# T03_Schematic.net
KiCad netlist of a schematic drawn in EAGLE
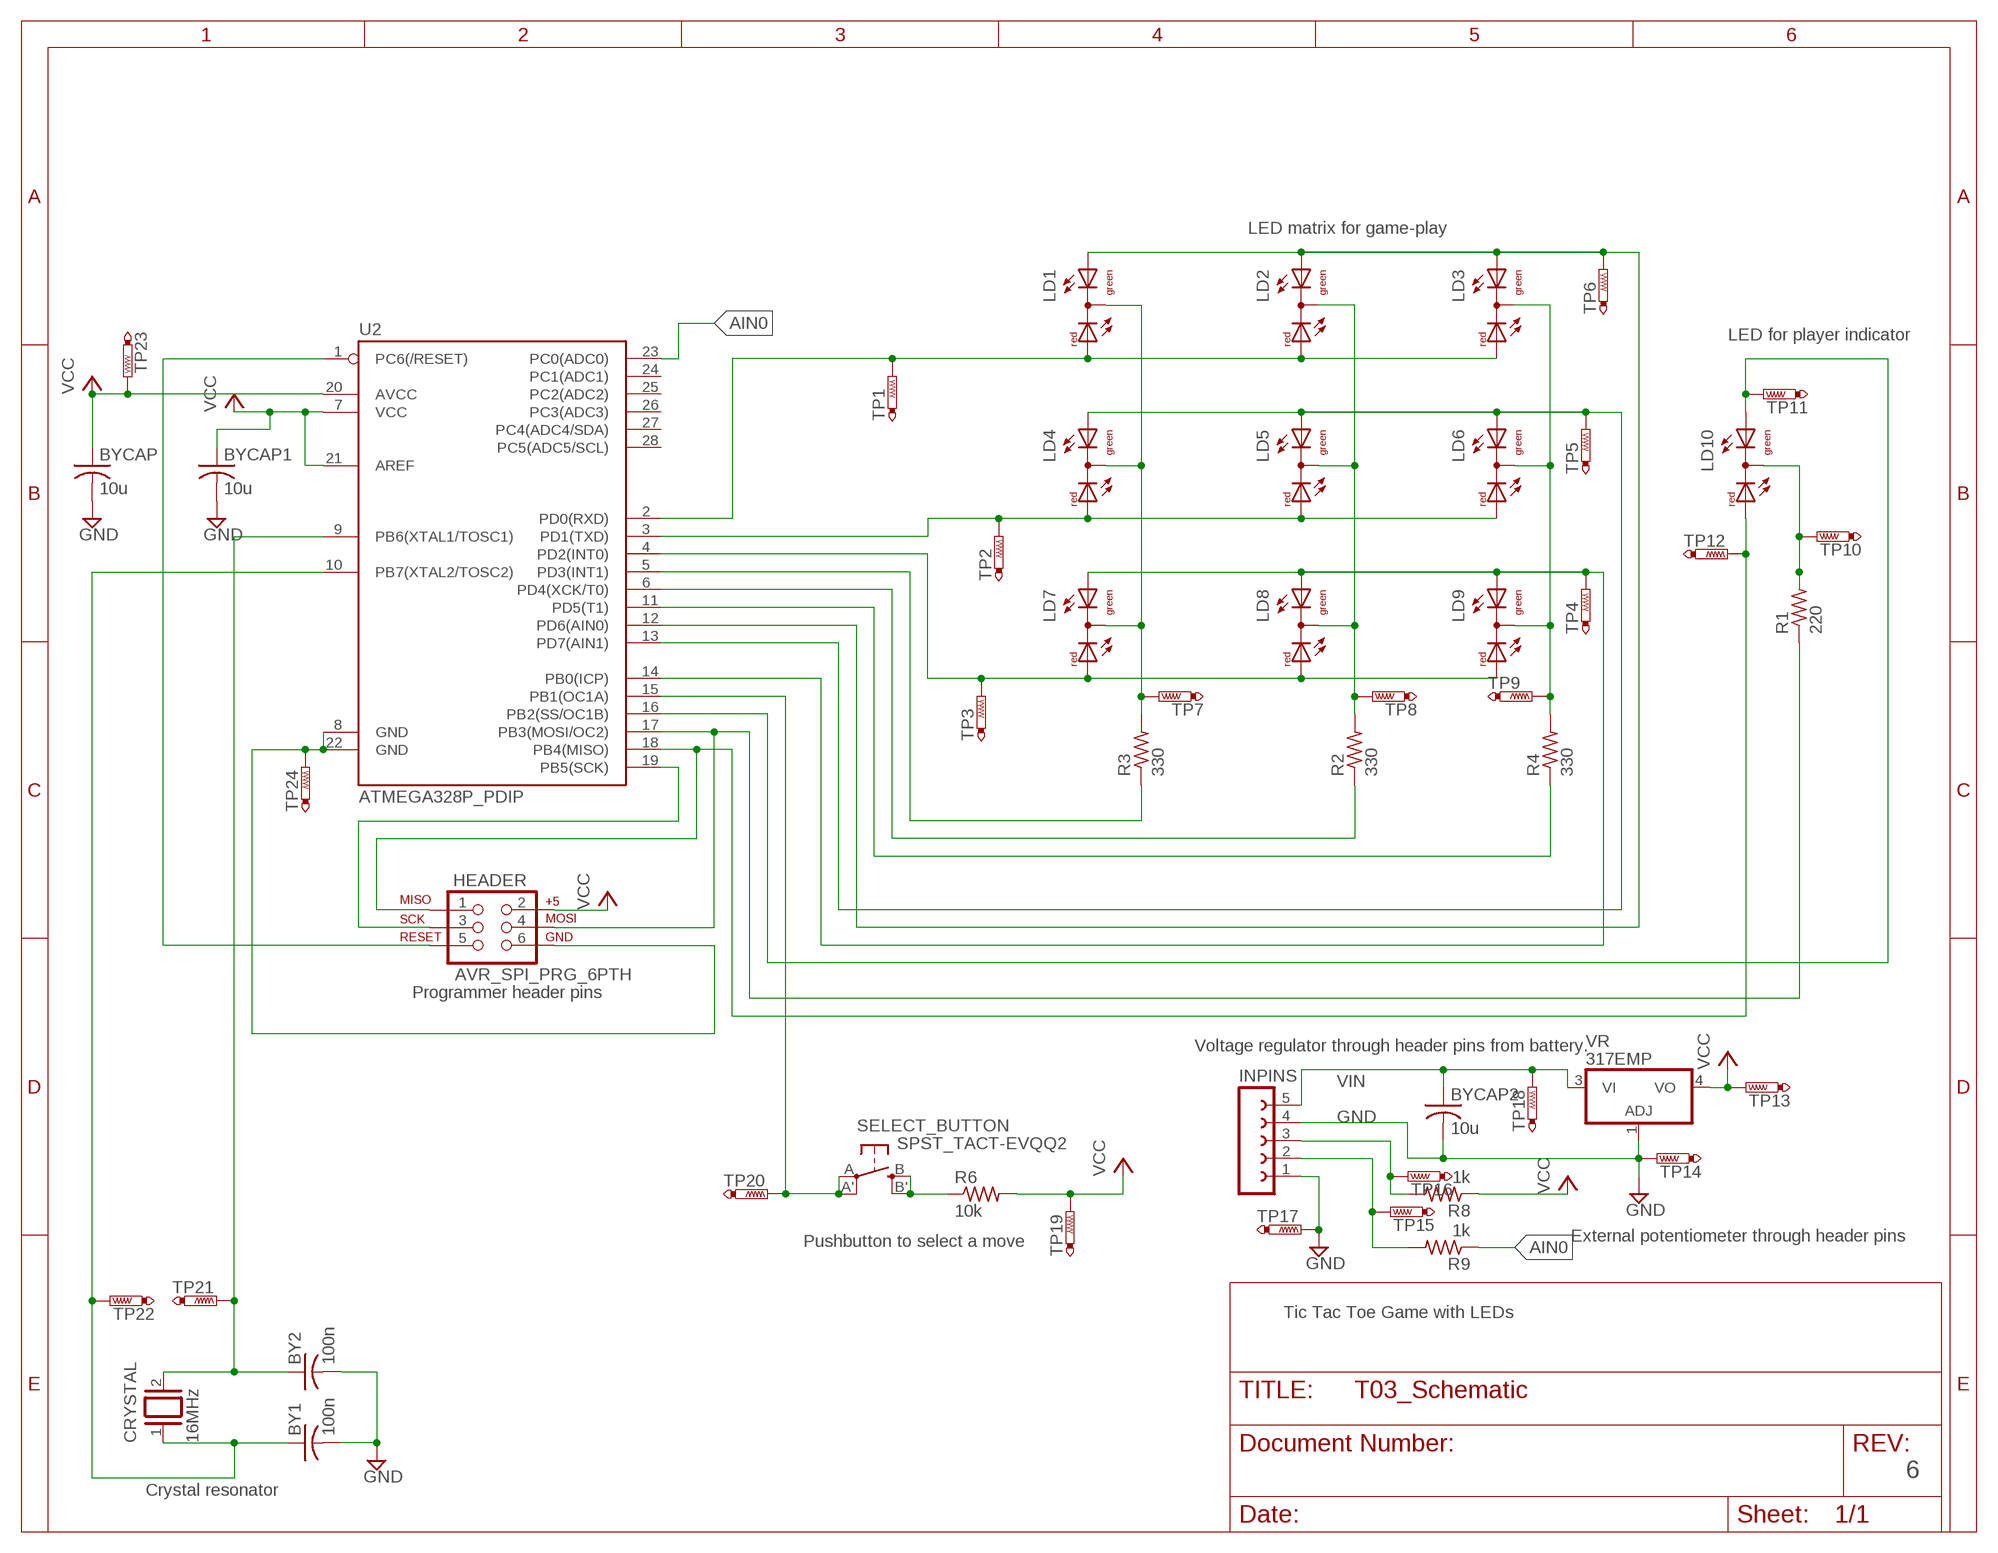
[diagram p0: schematic, sheet 1]

(export (version "E")
  (design (tool "Eeschema 10.0.6"))
  (components
    (comp (ref "BY1")
      (value "100n")
      (footprint "eagle-import:C0805")
      (libsource (lib "eagle-import") (part "C-USC0805"))
    )
    (comp (ref "BY2")
      (value "100n")
      (footprint "eagle-import:C0805")
      (libsource (lib "eagle-import") (part "C-USC0805"))
    )
    (comp (ref "BYCAP")
      (value "10u")
      (footprint "eagle-import:C0805")
      (libsource (lib "eagle-import") (part "C-USC0805"))
    )
    (comp (ref "BYCAP1")
      (value "10u")
      (footprint "eagle-import:C0805")
      (libsource (lib "eagle-import") (part "C-USC0805"))
    )
    (comp (ref "BYCAP2")
      (value "10u")
      (footprint "eagle-import:C0805")
      (libsource (lib "eagle-import") (part "C-USC0805"))
    )
    (comp (ref "CRYSTAL")
      (value "16MHz")
      (footprint "eagle-import:QS")
      (libsource (lib "eagle-import") (part "XTAL/S"))
    )
    (comp (ref "HEADER")
      (value "AVR_SPI_PRG_6PTH")
      (footprint "eagle-import:2X3")
      (libsource (lib "eagle-import") (part "AVR_SPI_PRG_6PTH"))
    )
    (comp (ref "INPINS")
      (value "FE05-1")
      (footprint "eagle-import:FE05-1")
      (libsource (lib "eagle-import") (part "FE05-1"))
    )
    (comp (ref "LD1")
      (value "DUOLED-RG-C")
      (footprint "eagle-import:DUOLED-C-5MM")
      (libsource (lib "eagle-import") (part "DUOLED-RG-C"))
    )
    (comp (ref "LD2")
      (value "DUOLED-RG-C")
      (footprint "eagle-import:DUOLED-C-5MM")
      (libsource (lib "eagle-import") (part "DUOLED-RG-C"))
    )
    (comp (ref "LD3")
      (value "DUOLED-RG-C")
      (footprint "eagle-import:DUOLED-C-5MM")
      (libsource (lib "eagle-import") (part "DUOLED-RG-C"))
    )
    (comp (ref "LD4")
      (value "DUOLED-RG-C")
      (footprint "eagle-import:DUOLED-C-5MM")
      (libsource (lib "eagle-import") (part "DUOLED-RG-C"))
    )
    (comp (ref "LD5")
      (value "DUOLED-RG-C")
      (footprint "eagle-import:DUOLED-C-5MM")
      (libsource (lib "eagle-import") (part "DUOLED-RG-C"))
    )
    (comp (ref "LD6")
      (value "DUOLED-RG-C")
      (footprint "eagle-import:DUOLED-C-5MM")
      (libsource (lib "eagle-import") (part "DUOLED-RG-C"))
    )
    (comp (ref "LD7")
      (value "DUOLED-RG-C")
      (footprint "eagle-import:DUOLED-C-5MM")
      (libsource (lib "eagle-import") (part "DUOLED-RG-C"))
    )
    (comp (ref "LD8")
      (value "DUOLED-RG-C")
      (footprint "eagle-import:DUOLED-C-5MM")
      (libsource (lib "eagle-import") (part "DUOLED-RG-C"))
    )
    (comp (ref "LD9")
      (value "DUOLED-RG-C")
      (footprint "eagle-import:DUOLED-C-5MM")
      (libsource (lib "eagle-import") (part "DUOLED-RG-C"))
    )
    (comp (ref "LD10")
      (value "DUOLED-RG-C")
      (footprint "eagle-import:DUOLED-C-5MM")
      (libsource (lib "eagle-import") (part "DUOLED-RG-C"))
    )
    (comp (ref "R1")
      (value "220")
      (footprint "eagle-import:M0805")
      (libsource (lib "eagle-import") (part "R-US_M0805"))
    )
    (comp (ref "R2")
      (value "330")
      (footprint "eagle-import:M0805")
      (libsource (lib "eagle-import") (part "R-US_M0805"))
    )
    (comp (ref "R3")
      (value "330")
      (footprint "eagle-import:M0805")
      (libsource (lib "eagle-import") (part "R-US_M0805"))
    )
    (comp (ref "R4")
      (value "330")
      (footprint "eagle-import:M0805")
      (libsource (lib "eagle-import") (part "R-US_M0805"))
    )
    (comp (ref "R6")
      (value "10k")
      (footprint "eagle-import:M0805")
      (libsource (lib "eagle-import") (part "R-US_M0805"))
    )
    (comp (ref "R8")
      (value "1k")
      (footprint "eagle-import:M0805")
      (libsource (lib "eagle-import") (part "R-US_M0805"))
    )
    (comp (ref "R9")
      (value "1k")
      (footprint "eagle-import:M0805")
      (libsource (lib "eagle-import") (part "R-US_M0805"))
    )
    (comp (ref "SELECT_BUTTON")
      (value "SPST_TACT-EVQQ2")
      (footprint "eagle-import:EVQ-Q2")
      (libsource (lib "eagle-import") (part "SPST_TACT-EVQQ2"))
    )
    (comp (ref "TP1")
      (value "PTR1B1,27")
      (footprint "eagle-import:B1,27")
      (libsource (lib "eagle-import") (part "PTR1B1,27"))
    )
    (comp (ref "TP2")
      (value "PTR1B1,27")
      (footprint "eagle-import:B1,27")
      (libsource (lib "eagle-import") (part "PTR1B1,27"))
    )
    (comp (ref "TP3")
      (value "PTR1B1,27")
      (footprint "eagle-import:B1,27")
      (libsource (lib "eagle-import") (part "PTR1B1,27"))
    )
    (comp (ref "TP4")
      (value "PTR1B1,27")
      (footprint "eagle-import:B1,27")
      (libsource (lib "eagle-import") (part "PTR1B1,27"))
    )
    (comp (ref "TP5")
      (value "PTR1B1,27")
      (footprint "eagle-import:B1,27")
      (libsource (lib "eagle-import") (part "PTR1B1,27"))
    )
    (comp (ref "TP6")
      (value "PTR1B1,27")
      (footprint "eagle-import:B1,27")
      (libsource (lib "eagle-import") (part "PTR1B1,27"))
    )
    (comp (ref "TP7")
      (value "PTR1B1,27")
      (footprint "eagle-import:B1,27")
      (libsource (lib "eagle-import") (part "PTR1B1,27"))
    )
    (comp (ref "TP8")
      (value "PTR1B1,27")
      (footprint "eagle-import:B1,27")
      (libsource (lib "eagle-import") (part "PTR1B1,27"))
    )
    (comp (ref "TP9")
      (value "PTR1B1,27")
      (footprint "eagle-import:B1,27")
      (libsource (lib "eagle-import") (part "PTR1B1,27"))
    )
    (comp (ref "TP10")
      (value "PTR1B1,27")
      (footprint "eagle-import:B1,27")
      (libsource (lib "eagle-import") (part "PTR1B1,27"))
    )
    (comp (ref "TP11")
      (value "PTR1B1,27")
      (footprint "eagle-import:B1,27")
      (libsource (lib "eagle-import") (part "PTR1B1,27"))
    )
    (comp (ref "TP12")
      (value "PTR1B1,27")
      (footprint "eagle-import:B1,27")
      (libsource (lib "eagle-import") (part "PTR1B1,27"))
    )
    (comp (ref "TP13")
      (value "PTR1B1,27")
      (footprint "eagle-import:B1,27")
      (libsource (lib "eagle-import") (part "PTR1B1,27"))
    )
    (comp (ref "TP14")
      (value "PTR1B1,27")
      (footprint "eagle-import:B1,27")
      (libsource (lib "eagle-import") (part "PTR1B1,27"))
    )
    (comp (ref "TP15")
      (value "PTR1B1,27")
      (footprint "eagle-import:B1,27")
      (libsource (lib "eagle-import") (part "PTR1B1,27"))
    )
    (comp (ref "TP16")
      (value "PTR1B1,27")
      (footprint "eagle-import:B1,27")
      (libsource (lib "eagle-import") (part "PTR1B1,27"))
    )
    (comp (ref "TP17")
      (value "PTR1B1,27")
      (footprint "eagle-import:B1,27")
      (libsource (lib "eagle-import") (part "PTR1B1,27"))
    )
    (comp (ref "TP18")
      (value "PTR1B1,27")
      (footprint "eagle-import:B1,27")
      (libsource (lib "eagle-import") (part "PTR1B1,27"))
    )
    (comp (ref "TP19")
      (value "PTR1B1,27")
      (footprint "eagle-import:B1,27")
      (libsource (lib "eagle-import") (part "PTR1B1,27"))
    )
    (comp (ref "TP20")
      (value "PTR1B1,27")
      (footprint "eagle-import:B1,27")
      (libsource (lib "eagle-import") (part "PTR1B1,27"))
    )
    (comp (ref "TP21")
      (value "PTR1B1,27")
      (footprint "eagle-import:B1,27")
      (libsource (lib "eagle-import") (part "PTR1B1,27"))
    )
    (comp (ref "TP22")
      (value "PTR1B1,27")
      (footprint "eagle-import:B1,27")
      (libsource (lib "eagle-import") (part "PTR1B1,27"))
    )
    (comp (ref "TP23")
      (value "PTR1B1,27")
      (footprint "eagle-import:B1,27")
      (libsource (lib "eagle-import") (part "PTR1B1,27"))
    )
    (comp (ref "TP24")
      (value "PTR1B1,27")
      (footprint "eagle-import:B1,27")
      (libsource (lib "eagle-import") (part "PTR1B1,27"))
    )
    (comp (ref "U2")
      (value "ATMEGA328P_PDIP")
      (footprint "eagle-import:DIL28-3")
      (libsource (lib "eagle-import") (part "ATMEGA328P_PDIP"))
    )
    (comp (ref "VR")
      (value "317EMP")
      (footprint "eagle-import:SOT223")
      (libsource (lib "eagle-import") (part "317EMP"))
    )
  )
  (nets
    (net (code "1") (name "/VIN") (class "Default")
      (node (ref "BYCAP2") (pin "1") (pinfunction "1_1") (pintype "passive"))
      (node (ref "INPINS") (pin "5") (pinfunction "5_5") (pintype "passive"))
      (node (ref "TP18") (pin "TP") (pinfunction "TP_TP") (pintype "input"))
      (node (ref "VR") (pin "3") (pinfunction "VI_3") (pintype "input"))
    )
    (net (code "2") (name "AIN0") (class "Default")
      (node (ref "R9") (pin "1") (pinfunction "1_1") (pintype "passive"))
      (node (ref "U2") (pin "23") (pinfunction "PC0(ADC0)_23") (pintype "bidirectional"))
    )
    (net (code "3") (name "GND") (class "Default")
      (node (ref "BY1") (pin "2") (pinfunction "2_2") (pintype "passive"))
      (node (ref "BY2") (pin "2") (pinfunction "2_2") (pintype "passive"))
      (node (ref "BYCAP") (pin "2") (pinfunction "2_2") (pintype "passive"))
      (node (ref "BYCAP1") (pin "2") (pinfunction "2_2") (pintype "passive"))
      (node (ref "BYCAP2") (pin "2") (pinfunction "2_2") (pintype "passive"))
      (node (ref "INPINS") (pin "1") (pinfunction "1_1") (pintype "passive"))
      (node (ref "INPINS") (pin "4") (pinfunction "4_4") (pintype "passive"))
      (node (ref "TP14") (pin "TP") (pinfunction "TP_TP") (pintype "input"))
      (node (ref "TP17") (pin "TP") (pinfunction "TP_TP") (pintype "input"))
      (node (ref "VR") (pin "1") (pinfunction "ADJ_1") (pintype "input"))
    )
    (net (code "4") (name "Net-(HEADER-Pad6)") (class "Default")
      (node (ref "HEADER") (pin "6") (pinfunction "6_6") (pintype "passive"))
      (node (ref "TP24") (pin "TP") (pinfunction "TP_TP") (pintype "input"))
      (node (ref "U2") (pin "22") (pinfunction "GND_22") (pintype "bidirectional"))
      (node (ref "U2") (pin "8") (pinfunction "GND_8") (pintype "bidirectional"))
    )
    (net (code "5") (name "Net-(INPINS-Pad2)") (class "Default")
      (node (ref "INPINS") (pin "2") (pinfunction "2_2") (pintype "passive"))
      (node (ref "R9") (pin "2") (pinfunction "2_2") (pintype "passive"))
      (node (ref "TP15") (pin "TP") (pinfunction "TP_TP") (pintype "input"))
    )
    (net (code "6") (name "Net-(INPINS-Pad3)") (class "Default")
      (node (ref "INPINS") (pin "3") (pinfunction "3_3") (pintype "passive"))
      (node (ref "R8") (pin "2") (pinfunction "2_2") (pintype "passive"))
      (node (ref "TP16") (pin "TP") (pinfunction "TP_TP") (pintype "input"))
    )
    (net (code "7") (name "Net-(LD1-AG)") (class "Default")
      (node (ref "LD1") (pin "AX") (pinfunction "AG_AX") (pintype "passive"))
      (node (ref "LD2") (pin "AX") (pinfunction "AG_AX") (pintype "passive"))
      (node (ref "LD3") (pin "AX") (pinfunction "AG_AX") (pintype "passive"))
      (node (ref "TP6") (pin "TP") (pinfunction "TP_TP") (pintype "input"))
      (node (ref "U2") (pin "12") (pinfunction "PD6(AIN0)_12") (pintype "bidirectional"))
    )
    (net (code "8") (name "Net-(LD1-PadC)") (class "Default")
      (node (ref "LD1") (pin "C") (pinfunction "C_C") (pintype "passive"))
      (node (ref "LD4") (pin "C") (pinfunction "C_C") (pintype "passive"))
      (node (ref "LD7") (pin "C") (pinfunction "C_C") (pintype "passive"))
      (node (ref "R3") (pin "2") (pinfunction "2_2") (pintype "passive"))
      (node (ref "TP7") (pin "TP") (pinfunction "TP_TP") (pintype "input"))
    )
    (net (code "9") (name "Net-(LD2-PadC)") (class "Default")
      (node (ref "LD2") (pin "C") (pinfunction "C_C") (pintype "passive"))
      (node (ref "LD5") (pin "C") (pinfunction "C_C") (pintype "passive"))
      (node (ref "LD8") (pin "C") (pinfunction "C_C") (pintype "passive"))
      (node (ref "R2") (pin "2") (pinfunction "2_2") (pintype "passive"))
      (node (ref "TP8") (pin "TP") (pinfunction "TP_TP") (pintype "input"))
    )
    (net (code "10") (name "Net-(LD3-PadC)") (class "Default")
      (node (ref "LD3") (pin "C") (pinfunction "C_C") (pintype "passive"))
      (node (ref "LD6") (pin "C") (pinfunction "C_C") (pintype "passive"))
      (node (ref "LD9") (pin "C") (pinfunction "C_C") (pintype "passive"))
      (node (ref "R4") (pin "2") (pinfunction "2_2") (pintype "passive"))
      (node (ref "TP9") (pin "TP") (pinfunction "TP_TP") (pintype "input"))
    )
    (net (code "11") (name "Net-(LD4-AG)") (class "Default")
      (node (ref "LD4") (pin "AX") (pinfunction "AG_AX") (pintype "passive"))
      (node (ref "LD5") (pin "AX") (pinfunction "AG_AX") (pintype "passive"))
      (node (ref "LD6") (pin "AX") (pinfunction "AG_AX") (pintype "passive"))
      (node (ref "TP5") (pin "TP") (pinfunction "TP_TP") (pintype "input"))
      (node (ref "U2") (pin "13") (pinfunction "PD7(AIN1)_13") (pintype "bidirectional"))
    )
    (net (code "12") (name "Net-(LD7-AG)") (class "Default")
      (node (ref "LD7") (pin "AX") (pinfunction "AG_AX") (pintype "passive"))
      (node (ref "LD8") (pin "AX") (pinfunction "AG_AX") (pintype "passive"))
      (node (ref "LD9") (pin "AX") (pinfunction "AG_AX") (pintype "passive"))
      (node (ref "TP4") (pin "TP") (pinfunction "TP_TP") (pintype "input"))
      (node (ref "U2") (pin "14") (pinfunction "PB0(ICP)_14") (pintype "bidirectional"))
    )
    (net (code "13") (name "Net-(LD10-AG)") (class "Default")
      (node (ref "LD10") (pin "AX") (pinfunction "AG_AX") (pintype "passive"))
      (node (ref "TP11") (pin "TP") (pinfunction "TP_TP") (pintype "input"))
      (node (ref "U2") (pin "16") (pinfunction "PB2(SS/OC1B)_16") (pintype "bidirectional"))
    )
    (net (code "14") (name "Net-(LD10-PadC)") (class "Default")
      (node (ref "LD10") (pin "C") (pinfunction "C_C") (pintype "passive"))
      (node (ref "R1") (pin "2") (pinfunction "2_2") (pintype "passive"))
      (node (ref "TP10") (pin "TP") (pinfunction "TP_TP") (pintype "input"))
    )
    (net (code "15") (name "Net-(SELECT_BUTTON-P)") (class "Default")
      (node (ref "SELECT_BUTTON") (pin "A") (pinfunction "P_A") (pintype "passive"))
      (node (ref "SELECT_BUTTON") (pin "A'") (pinfunction "P1_A'") (pintype "passive"))
      (node (ref "TP20") (pin "TP") (pinfunction "TP_TP") (pintype "input"))
      (node (ref "U2") (pin "15") (pinfunction "PB1(OC1A)_15") (pintype "bidirectional"))
    )
    (net (code "16") (name "Net-(SELECT_BUTTON-S)") (class "Default")
      (node (ref "R6") (pin "1") (pinfunction "1_1") (pintype "passive"))
      (node (ref "SELECT_BUTTON") (pin "B") (pinfunction "S_B") (pintype "passive"))
      (node (ref "SELECT_BUTTON") (pin "B'") (pinfunction "S1_B'") (pintype "passive"))
    )
    (net (code "17") (name "Net-(U2-PB3(MOSI{slash}OC2))") (class "Default")
      (node (ref "HEADER") (pin "4") (pinfunction "4_4") (pintype "passive"))
      (node (ref "R1") (pin "1") (pinfunction "1_1") (pintype "passive"))
      (node (ref "U2") (pin "17") (pinfunction "PB3(MOSI/OC2)_17") (pintype "bidirectional"))
    )
    (net (code "18") (name "Net-(U2-PB4(MISO))") (class "Default")
      (node (ref "HEADER") (pin "1") (pinfunction "1_1") (pintype "passive"))
      (node (ref "LD10") (pin "AR") (pinfunction "AR_AR") (pintype "passive"))
      (node (ref "TP12") (pin "TP") (pinfunction "TP_TP") (pintype "input"))
      (node (ref "U2") (pin "18") (pinfunction "PB4(MISO)_18") (pintype "bidirectional"))
    )
    (net (code "19") (name "Net-(U2-PB5(SCK))") (class "Default")
      (node (ref "HEADER") (pin "3") (pinfunction "3_3") (pintype "passive"))
      (node (ref "U2") (pin "19") (pinfunction "PB5(SCK)_19") (pintype "bidirectional"))
    )
    (net (code "20") (name "Net-(U2-PB6(XTAL1{slash}TOSC1))") (class "Default")
      (node (ref "BY2") (pin "1") (pinfunction "1_1") (pintype "passive"))
      (node (ref "CRYSTAL") (pin "2") (pinfunction "2_2") (pintype "passive"))
      (node (ref "TP21") (pin "TP") (pinfunction "TP_TP") (pintype "input"))
      (node (ref "U2") (pin "9") (pinfunction "PB6(XTAL1/TOSC1)_9") (pintype "bidirectional"))
    )
    (net (code "21") (name "Net-(U2-PB7(XTAL2{slash}TOSC2))") (class "Default")
      (node (ref "BY1") (pin "1") (pinfunction "1_1") (pintype "passive"))
      (node (ref "CRYSTAL") (pin "1") (pinfunction "1_1") (pintype "passive"))
      (node (ref "TP22") (pin "TP") (pinfunction "TP_TP") (pintype "input"))
      (node (ref "U2") (pin "10") (pinfunction "PB7(XTAL2/TOSC2)_10") (pintype "bidirectional"))
    )
    (net (code "22") (name "Net-(U2-PC6({slash}RESET))") (class "Default")
      (node (ref "HEADER") (pin "5") (pinfunction "5_5") (pintype "passive"))
      (node (ref "U2") (pin "1") (pinfunction "PC6(/RESET)_1") (pintype "bidirectional"))
    )
    (net (code "23") (name "Net-(U2-PD0(RXD))") (class "Default")
      (node (ref "LD1") (pin "AR") (pinfunction "AR_AR") (pintype "passive"))
      (node (ref "LD2") (pin "AR") (pinfunction "AR_AR") (pintype "passive"))
      (node (ref "LD3") (pin "AR") (pinfunction "AR_AR") (pintype "passive"))
      (node (ref "TP1") (pin "TP") (pinfunction "TP_TP") (pintype "input"))
      (node (ref "U2") (pin "2") (pinfunction "PD0(RXD)_2") (pintype "bidirectional"))
    )
    (net (code "24") (name "Net-(U2-PD1(TXD))") (class "Default")
      (node (ref "LD4") (pin "AR") (pinfunction "AR_AR") (pintype "passive"))
      (node (ref "LD5") (pin "AR") (pinfunction "AR_AR") (pintype "passive"))
      (node (ref "LD6") (pin "AR") (pinfunction "AR_AR") (pintype "passive"))
      (node (ref "TP2") (pin "TP") (pinfunction "TP_TP") (pintype "input"))
      (node (ref "U2") (pin "3") (pinfunction "PD1(TXD)_3") (pintype "bidirectional"))
    )
    (net (code "25") (name "Net-(U2-PD2(INT0))") (class "Default")
      (node (ref "LD7") (pin "AR") (pinfunction "AR_AR") (pintype "passive"))
      (node (ref "LD8") (pin "AR") (pinfunction "AR_AR") (pintype "passive"))
      (node (ref "LD9") (pin "AR") (pinfunction "AR_AR") (pintype "passive"))
      (node (ref "TP3") (pin "TP") (pinfunction "TP_TP") (pintype "input"))
      (node (ref "U2") (pin "4") (pinfunction "PD2(INT0)_4") (pintype "bidirectional"))
    )
    (net (code "26") (name "Net-(U2-PD3(INT1))") (class "Default")
      (node (ref "R3") (pin "1") (pinfunction "1_1") (pintype "passive"))
      (node (ref "U2") (pin "5") (pinfunction "PD3(INT1)_5") (pintype "bidirectional"))
    )
    (net (code "27") (name "Net-(U2-PD4(XCK{slash}T0))") (class "Default")
      (node (ref "R2") (pin "1") (pinfunction "1_1") (pintype "passive"))
      (node (ref "U2") (pin "6") (pinfunction "PD4(XCK/T0)_6") (pintype "bidirectional"))
    )
    (net (code "28") (name "Net-(U2-PD5(T1))") (class "Default")
      (node (ref "R4") (pin "1") (pinfunction "1_1") (pintype "passive"))
      (node (ref "U2") (pin "11") (pinfunction "PD5(T1)_11") (pintype "bidirectional"))
    )
    (net (code "29") (name "VCC") (class "Default")
      (node (ref "BYCAP") (pin "1") (pinfunction "1_1") (pintype "passive"))
      (node (ref "BYCAP1") (pin "1") (pinfunction "1_1") (pintype "passive"))
      (node (ref "HEADER") (pin "2") (pinfunction "2_2") (pintype "passive"))
      (node (ref "R6") (pin "2") (pinfunction "2_2") (pintype "passive"))
      (node (ref "R8") (pin "1") (pinfunction "1_1") (pintype "passive"))
      (node (ref "TP13") (pin "TP") (pinfunction "TP_TP") (pintype "input"))
      (node (ref "TP19") (pin "TP") (pinfunction "TP_TP") (pintype "input"))
      (node (ref "TP23") (pin "TP") (pinfunction "TP_TP") (pintype "input"))
      (node (ref "U2") (pin "20") (pinfunction "AVCC_20") (pintype "bidirectional"))
      (node (ref "U2") (pin "21") (pinfunction "AREF_21") (pintype "bidirectional"))
      (node (ref "U2") (pin "7") (pinfunction "VCC_7") (pintype "bidirectional"))
      (node (ref "VR") (pin "4") (pinfunction "VO_4") (pintype "passive"))
    )
    (net (code "30") (name "unconnected-(U2-PC1(ADC1)-Pad24)") (class "Default")
      (node (ref "U2") (pin "24") (pinfunction "PC1(ADC1)_24") (pintype "bidirectional"))
    )
    (net (code "31") (name "unconnected-(U2-PC2(ADC2)-Pad25)") (class "Default")
      (node (ref "U2") (pin "25") (pinfunction "PC2(ADC2)_25") (pintype "bidirectional"))
    )
    (net (code "32") (name "unconnected-(U2-PC3(ADC3)-Pad26)") (class "Default")
      (node (ref "U2") (pin "26") (pinfunction "PC3(ADC3)_26") (pintype "bidirectional"))
    )
    (net (code "33") (name "unconnected-(U2-PC4(ADC4{slash}SDA)-Pad27)") (class "Default")
      (node (ref "U2") (pin "27") (pinfunction "PC4(ADC4/SDA)_27") (pintype "bidirectional"))
    )
    (net (code "34") (name "unconnected-(U2-PC5(ADC5{slash}SCL)-Pad28)") (class "Default")
      (node (ref "U2") (pin "28") (pinfunction "PC5(ADC5/SCL)_28") (pintype "bidirectional"))
    )
  )
)
